# Main.net
KiCad netlist of a schematic drawn in Altium Designer
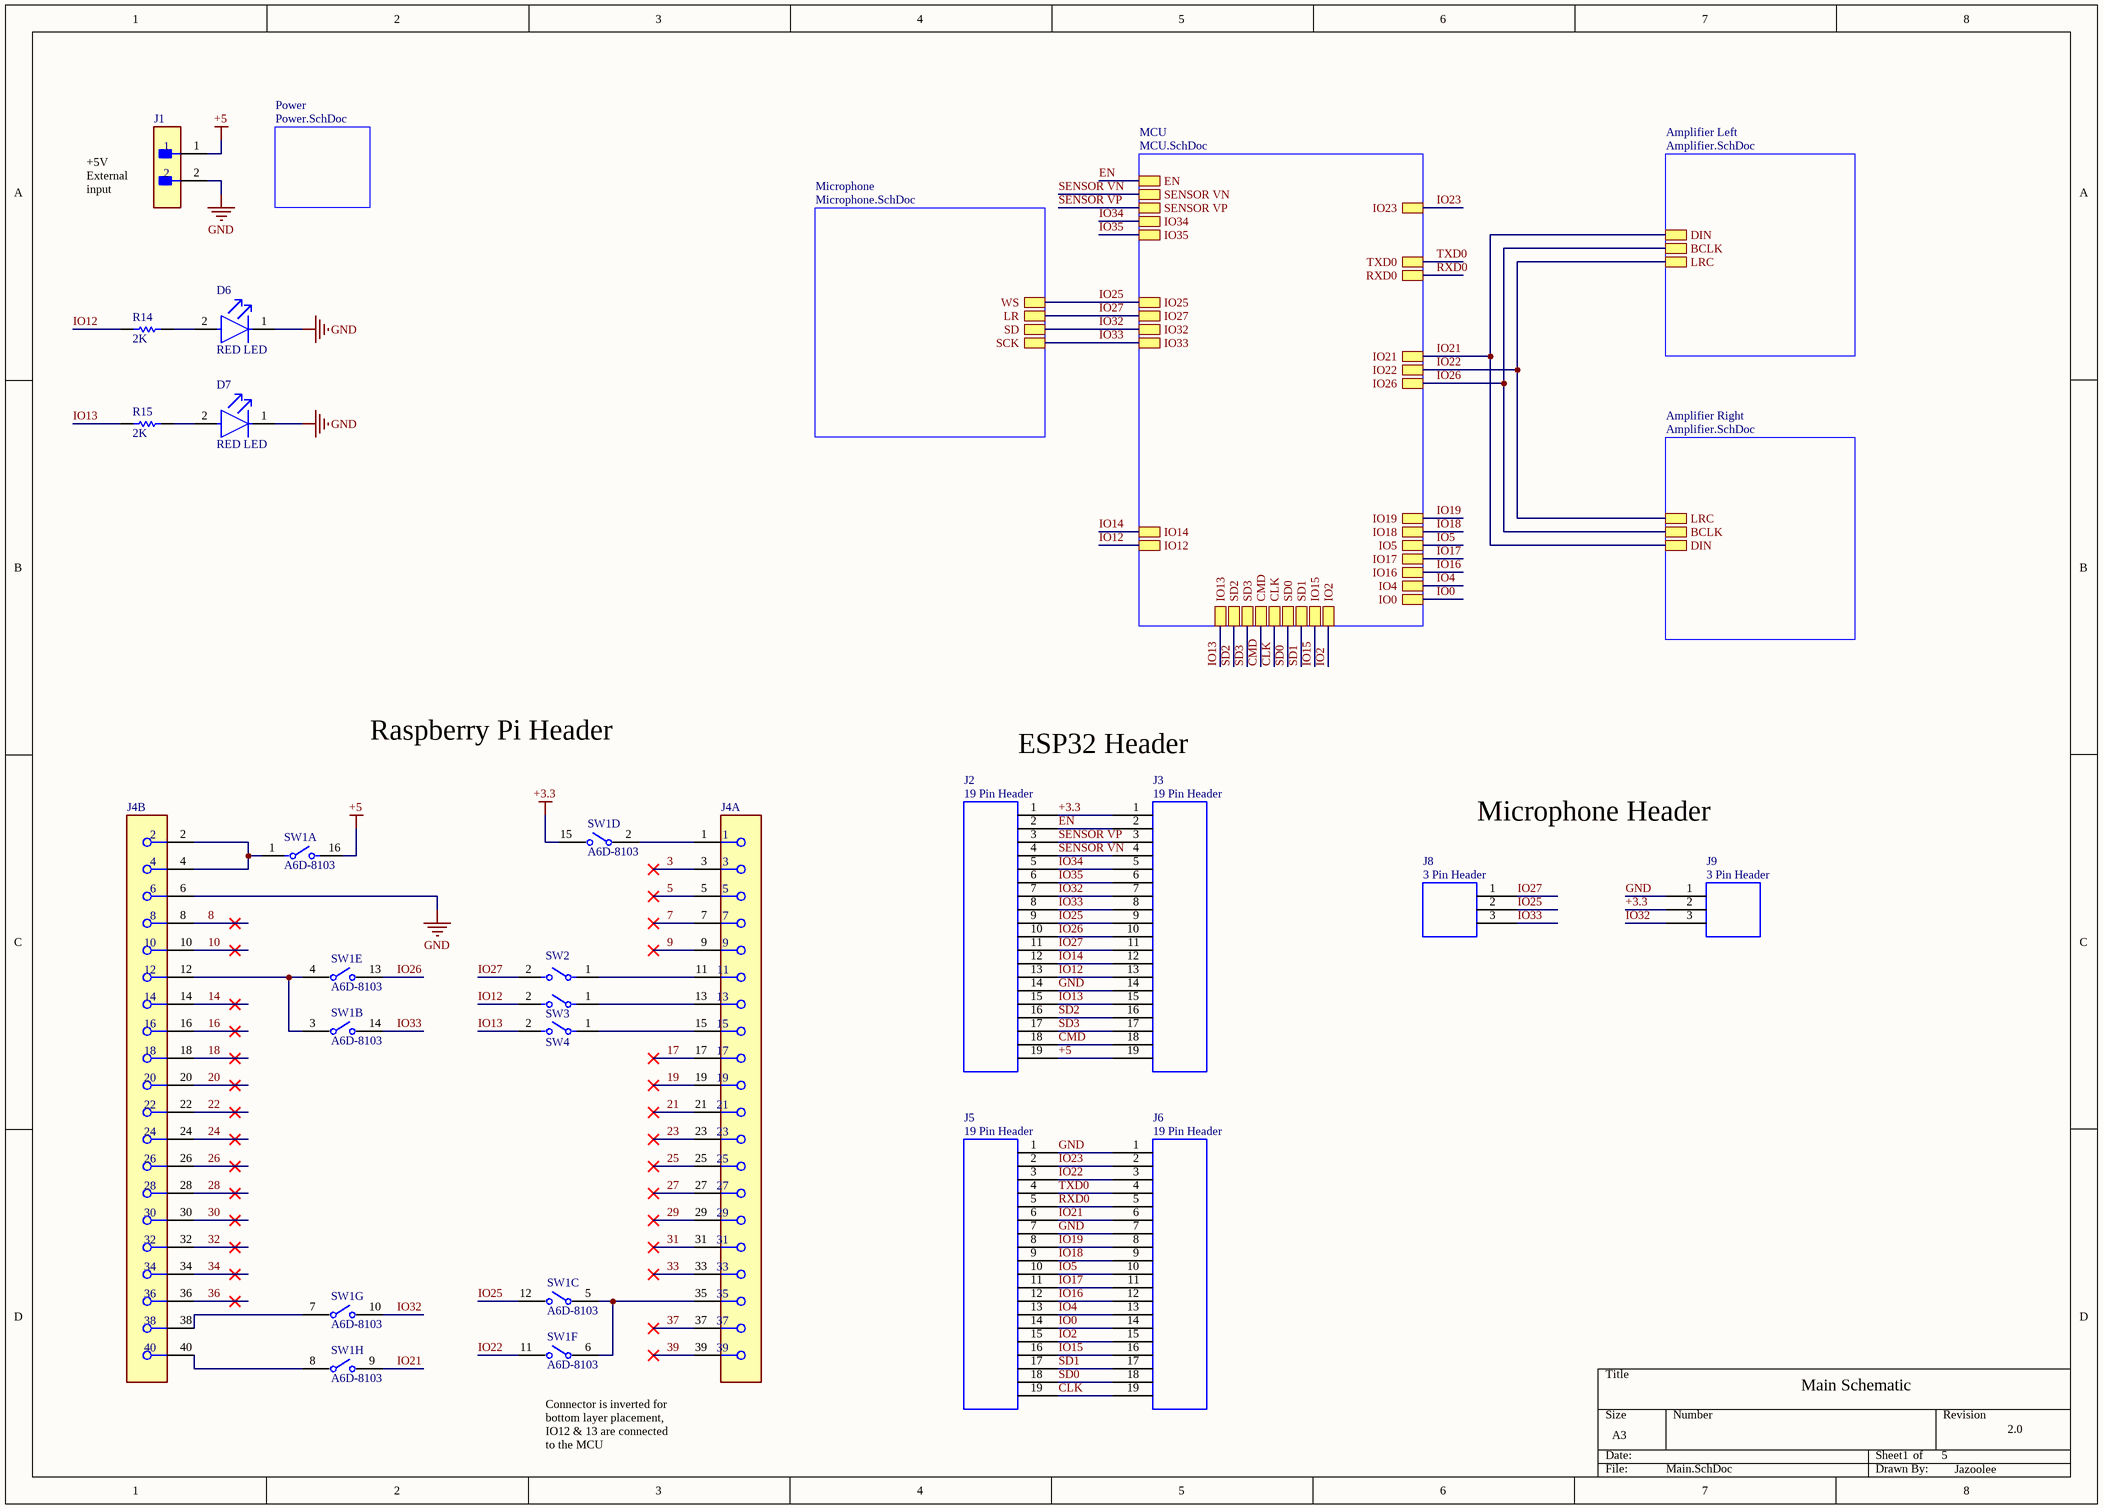
[diagram p0: Main.SchDoc]

(export (version "E")
  (design (tool "Eeschema 10.0.6"))
  (components
    (comp (ref "D6")
      (value "HSMS-C150")
      (footprint "FP-HSMS-C150-MFG")
      (description "LED RED")
      (fields (field (name "COLOR") "RED LED"))
      (libsource (lib "Altium Content Vault") (part "8706943c75ba83719d021d2fdc84c58"))
    )
    (comp (ref "D7")
      (value "HSMS-C150")
      (footprint "FP-HSMS-C150-MFG")
      (description "LED RED")
      (fields (field (name "COLOR") "RED LED"))
      (libsource (lib "Altium Content Vault") (part "8706943c75ba83719d021d2fdc84c58"))
    )
    (comp (ref "J1")
      (value "B2B-XH-A(LF)(SN)")
      (footprint "FP-B2B-XH-A_LF_SN-MFG")
      (description "CONN HEADER VERT 2POS 2.5MM")
      (libsource (lib "Altium Content Vault") (part "3bc925449376181038e59eaffc5286c"))
    )
    (comp (ref "J2")
      (value "19 Pin Header")
      (footprint "19 Pin Header")
      (libsource (lib "Schlib1") (part "19 Pin Header"))
    )
    (comp (ref "J3")
      (value "19 Pin Header")
      (footprint "19 Pin Header")
      (libsource (lib "Schlib1") (part "19 Pin Header"))
    )
    (comp (ref "J4")
      (value "SFH11-PBPC-D20-ST-BK")
      (footprint "FP-SFH11-PBPC-D20-ST-BK-MFG")
      (description "CONN HDR 40POS 0.1 GOLD PCB")
      (libsource (lib "Altium Content Vault") (part "7acf1c4a8db21028d11741a46a6ec78"))
    )
    (comp (ref "J5")
      (value "19 Pin Header")
      (footprint "19 Pin Header")
      (libsource (lib "Schlib1") (part "19 Pin Header"))
    )
    (comp (ref "J6")
      (value "19 Pin Header")
      (footprint "19 Pin Header")
      (libsource (lib "Schlib1") (part "19 Pin Header"))
    )
    (comp (ref "J8")
      (value "3 Pin Header")
      (footprint "3 Pin Header")
      (libsource (lib "Schlib1") (part "3 Pin Header"))
    )
    (comp (ref "J9")
      (value "3 Pin Header")
      (footprint "3 Pin Header")
      (libsource (lib "Schlib1") (part "3 Pin Header"))
    )
    (comp (ref "R14")
      (value "2K")
      (footprint "RESC2013X60X35LL10T20")
      (fields (field (name "PART NUMBER") "RT0805FRE072KL") (field (name "MANUFACTURER") "Yageo"))
      (libsource (lib "Altium Content Vault") (part "RES"))
    )
    (comp (ref "R15")
      (value "2K")
      (footprint "RESC2013X60X35LL10T20")
      (fields (field (name "PART NUMBER") "RT0805FRE072KL") (field (name "MANUFACTURER") "Yageo"))
      (libsource (lib "Altium Content Vault") (part "RES"))
    )
    (comp (ref "SW1")
      (value "A6D-8103")
      (footprint "FP-A6D-8103-MFG")
      (description "SWITCH SLIDE DIP SPST 30MA 30V")
      (fields
        (field (name "MANUFACTURER") "Omron Electronics Inc-EMC Div")
        (field (name "OCTOPART") "https://octopart.com/a6d-8103-omron-134189")
      )
      (libsource (lib "Altium Content Vault") (part "05751733197cf25f22959cb843bf489"))
    )
    (comp (ref "SW2")
      (value "BD01")
      (footprint "FP-BD01-MFG")
      (description "SWITCH SLIDE DIP SPST 100MA 5V")
      (libsource (lib "Altium Content Vault") (part "bb27bde45df87f1f469753f287ef5ae"))
    )
    (comp (ref "SW3")
      (value "BD01")
      (footprint "FP-BD01-MFG")
      (description "SWITCH SLIDE DIP SPST 100MA 5V")
      (libsource (lib "Altium Content Vault") (part "bb27bde45df87f1f469753f287ef5ae"))
    )
    (comp (ref "SW4")
      (value "BD01")
      (footprint "FP-BD01-MFG")
      (description "SWITCH SLIDE DIP SPST 100MA 5V")
      (libsource (lib "Altium Content Vault") (part "bb27bde45df87f1f469753f287ef5ae"))
    )
  )
  (nets
    (net (code "1") (name "+3.3") (class "Default")
      (node (ref "J2") (pin "1") (pinfunction "1_1") (pintype "passive"))
      (node (ref "J3") (pin "1") (pinfunction "1_1") (pintype "passive"))
      (node (ref "J9") (pin "2") (pinfunction "2_2") (pintype "passive"))
      (node (ref "SW1") (pin "15") (pinfunction "15_15") (pintype "passive"))
    )
    (net (code "2") (name "+5") (class "Default")
      (node (ref "J1") (pin "1") (pinfunction "1_1") (pintype "passive"))
      (node (ref "J2") (pin "19") (pinfunction "19_19") (pintype "passive"))
      (node (ref "J3") (pin "19") (pinfunction "19_19") (pintype "passive"))
      (node (ref "SW1") (pin "16") (pinfunction "16_16") (pintype "passive"))
    )
    (net (code "3") (name "/3") (class "Default")
      (node (ref "J4") (pin "3") (pinfunction "3_3") (pintype "passive+no_connect"))
    )
    (net (code "4") (name "/5") (class "Default")
      (node (ref "J4") (pin "5") (pinfunction "5_5") (pintype "passive+no_connect"))
    )
    (net (code "5") (name "/7") (class "Default")
      (node (ref "J4") (pin "7") (pinfunction "7_7") (pintype "passive+no_connect"))
    )
    (net (code "6") (name "/8") (class "Default")
      (node (ref "J4") (pin "8") (pinfunction "8_8") (pintype "passive"))
    )
    (net (code "7") (name "/9") (class "Default")
      (node (ref "J4") (pin "9") (pinfunction "9_9") (pintype "passive+no_connect"))
    )
    (net (code "8") (name "/10") (class "Default")
      (node (ref "J4") (pin "10") (pinfunction "10_10") (pintype "passive"))
    )
    (net (code "9") (name "/14") (class "Default")
      (node (ref "J4") (pin "14") (pinfunction "14_14") (pintype "passive"))
    )
    (net (code "10") (name "/16") (class "Default")
      (node (ref "J4") (pin "16") (pinfunction "16_16") (pintype "passive"))
    )
    (net (code "11") (name "/17") (class "Default")
      (node (ref "J4") (pin "17") (pinfunction "17_17") (pintype "passive+no_connect"))
    )
    (net (code "12") (name "/18") (class "Default")
      (node (ref "J4") (pin "18") (pinfunction "18_18") (pintype "passive"))
    )
    (net (code "13") (name "/19") (class "Default")
      (node (ref "J4") (pin "19") (pinfunction "19_19") (pintype "passive+no_connect"))
    )
    (net (code "14") (name "/20") (class "Default")
      (node (ref "J4") (pin "20") (pinfunction "20_20") (pintype "passive"))
    )
    (net (code "15") (name "/21") (class "Default")
      (node (ref "J4") (pin "21") (pinfunction "21_21") (pintype "passive+no_connect"))
    )
    (net (code "16") (name "/22") (class "Default")
      (node (ref "J4") (pin "22") (pinfunction "22_22") (pintype "passive"))
    )
    (net (code "17") (name "/23") (class "Default")
      (node (ref "J4") (pin "23") (pinfunction "23_23") (pintype "passive+no_connect"))
    )
    (net (code "18") (name "/24") (class "Default")
      (node (ref "J4") (pin "24") (pinfunction "24_24") (pintype "passive"))
    )
    (net (code "19") (name "/25") (class "Default")
      (node (ref "J4") (pin "25") (pinfunction "25_25") (pintype "passive+no_connect"))
    )
    (net (code "20") (name "/26") (class "Default")
      (node (ref "J4") (pin "26") (pinfunction "26_26") (pintype "passive"))
    )
    (net (code "21") (name "/27") (class "Default")
      (node (ref "J4") (pin "27") (pinfunction "27_27") (pintype "passive+no_connect"))
    )
    (net (code "22") (name "/28") (class "Default")
      (node (ref "J4") (pin "28") (pinfunction "28_28") (pintype "passive"))
    )
    (net (code "23") (name "/29") (class "Default")
      (node (ref "J4") (pin "29") (pinfunction "29_29") (pintype "passive+no_connect"))
    )
    (net (code "24") (name "/30") (class "Default")
      (node (ref "J4") (pin "30") (pinfunction "30_30") (pintype "passive"))
    )
    (net (code "25") (name "/31") (class "Default")
      (node (ref "J4") (pin "31") (pinfunction "31_31") (pintype "passive+no_connect"))
    )
    (net (code "26") (name "/32") (class "Default")
      (node (ref "J4") (pin "32") (pinfunction "32_32") (pintype "passive"))
    )
    (net (code "27") (name "/33") (class "Default")
      (node (ref "J4") (pin "33") (pinfunction "33_33") (pintype "passive+no_connect"))
    )
    (net (code "28") (name "/34") (class "Default")
      (node (ref "J4") (pin "34") (pinfunction "34_34") (pintype "passive"))
    )
    (net (code "29") (name "/36") (class "Default")
      (node (ref "J4") (pin "36") (pinfunction "36_36") (pintype "passive"))
    )
    (net (code "30") (name "/37") (class "Default")
      (node (ref "J4") (pin "37") (pinfunction "37_37") (pintype "passive+no_connect"))
    )
    (net (code "31") (name "/39") (class "Default")
      (node (ref "J4") (pin "39") (pinfunction "39_39") (pintype "passive+no_connect"))
    )
    (net (code "32") (name "/CLK") (class "Default")
      (node (ref "J5") (pin "19") (pinfunction "19_19") (pintype "passive"))
      (node (ref "J6") (pin "19") (pinfunction "19_19") (pintype "passive"))
    )
    (net (code "33") (name "/CMD") (class "Default")
      (node (ref "J2") (pin "18") (pinfunction "18_18") (pintype "passive"))
      (node (ref "J3") (pin "18") (pinfunction "18_18") (pintype "passive"))
    )
    (net (code "34") (name "/EN") (class "Default")
      (node (ref "J2") (pin "2") (pinfunction "2_2") (pintype "passive"))
      (node (ref "J3") (pin "2") (pinfunction "2_2") (pintype "passive"))
    )
    (net (code "35") (name "/IO0") (class "Default")
      (node (ref "J5") (pin "14") (pinfunction "14_14") (pintype "passive"))
      (node (ref "J6") (pin "14") (pinfunction "14_14") (pintype "passive"))
    )
    (net (code "36") (name "/IO2") (class "Default")
      (node (ref "J5") (pin "15") (pinfunction "15_15") (pintype "passive"))
      (node (ref "J6") (pin "15") (pinfunction "15_15") (pintype "passive"))
    )
    (net (code "37") (name "/IO4") (class "Default")
      (node (ref "J5") (pin "13") (pinfunction "13_13") (pintype "passive"))
      (node (ref "J6") (pin "13") (pinfunction "13_13") (pintype "passive"))
    )
    (net (code "38") (name "/IO5") (class "Default")
      (node (ref "J5") (pin "10") (pinfunction "10_10") (pintype "passive"))
      (node (ref "J6") (pin "10") (pinfunction "10_10") (pintype "passive"))
    )
    (net (code "39") (name "/IO12") (class "Default")
      (node (ref "J2") (pin "13") (pinfunction "13_13") (pintype "passive"))
      (node (ref "J3") (pin "13") (pinfunction "13_13") (pintype "passive"))
      (node (ref "R14") (pin "2") (pinfunction "2_2") (pintype "passive"))
      (node (ref "SW3") (pin "2") (pinfunction "2_2") (pintype "passive"))
    )
    (net (code "40") (name "/IO13") (class "Default")
      (node (ref "J2") (pin "15") (pinfunction "15_15") (pintype "passive"))
      (node (ref "J3") (pin "15") (pinfunction "15_15") (pintype "passive"))
      (node (ref "R15") (pin "2") (pinfunction "2_2") (pintype "passive"))
      (node (ref "SW4") (pin "2") (pinfunction "2_2") (pintype "passive"))
    )
    (net (code "41") (name "/IO14") (class "Default")
      (node (ref "J2") (pin "12") (pinfunction "12_12") (pintype "passive"))
      (node (ref "J3") (pin "12") (pinfunction "12_12") (pintype "passive"))
    )
    (net (code "42") (name "/IO15") (class "Default")
      (node (ref "J5") (pin "16") (pinfunction "16_16") (pintype "passive"))
      (node (ref "J6") (pin "16") (pinfunction "16_16") (pintype "passive"))
    )
    (net (code "43") (name "/IO16") (class "Default")
      (node (ref "J5") (pin "12") (pinfunction "12_12") (pintype "passive"))
      (node (ref "J6") (pin "12") (pinfunction "12_12") (pintype "passive"))
    )
    (net (code "44") (name "/IO17") (class "Default")
      (node (ref "J5") (pin "11") (pinfunction "11_11") (pintype "passive"))
      (node (ref "J6") (pin "11") (pinfunction "11_11") (pintype "passive"))
    )
    (net (code "45") (name "/IO18") (class "Default")
      (node (ref "J5") (pin "9") (pinfunction "9_9") (pintype "passive"))
      (node (ref "J6") (pin "9") (pinfunction "9_9") (pintype "passive"))
    )
    (net (code "46") (name "/IO19") (class "Default")
      (node (ref "J5") (pin "8") (pinfunction "8_8") (pintype "passive"))
      (node (ref "J6") (pin "8") (pinfunction "8_8") (pintype "passive"))
    )
    (net (code "47") (name "/IO21") (class "Default")
      (node (ref "J5") (pin "6") (pinfunction "6_6") (pintype "passive"))
      (node (ref "J6") (pin "6") (pinfunction "6_6") (pintype "passive"))
      (node (ref "SW1") (pin "9") (pinfunction "9_9") (pintype "passive"))
    )
    (net (code "48") (name "/IO22") (class "Default")
      (node (ref "J5") (pin "3") (pinfunction "3_3") (pintype "passive"))
      (node (ref "J6") (pin "3") (pinfunction "3_3") (pintype "passive"))
      (node (ref "SW1") (pin "11") (pinfunction "11_11") (pintype "passive"))
    )
    (net (code "49") (name "/IO23") (class "Default")
      (node (ref "J5") (pin "2") (pinfunction "2_2") (pintype "passive"))
      (node (ref "J6") (pin "2") (pinfunction "2_2") (pintype "passive"))
    )
    (net (code "50") (name "/IO25") (class "Default")
      (node (ref "J2") (pin "9") (pinfunction "9_9") (pintype "passive"))
      (node (ref "J3") (pin "9") (pinfunction "9_9") (pintype "passive"))
      (node (ref "J8") (pin "2") (pinfunction "2_2") (pintype "passive"))
      (node (ref "SW1") (pin "12") (pinfunction "12_12") (pintype "passive"))
    )
    (net (code "51") (name "/IO26") (class "Default")
      (node (ref "J2") (pin "10") (pinfunction "10_10") (pintype "passive"))
      (node (ref "J3") (pin "10") (pinfunction "10_10") (pintype "passive"))
      (node (ref "SW1") (pin "13") (pinfunction "13_13") (pintype "passive"))
    )
    (net (code "52") (name "/IO27") (class "Default")
      (node (ref "J2") (pin "11") (pinfunction "11_11") (pintype "passive"))
      (node (ref "J3") (pin "11") (pinfunction "11_11") (pintype "passive"))
      (node (ref "J8") (pin "1") (pinfunction "1_1") (pintype "passive"))
      (node (ref "SW2") (pin "2") (pinfunction "2_2") (pintype "passive"))
    )
    (net (code "53") (name "/IO32") (class "Default")
      (node (ref "J2") (pin "7") (pinfunction "7_7") (pintype "passive"))
      (node (ref "J3") (pin "7") (pinfunction "7_7") (pintype "passive"))
      (node (ref "J9") (pin "3") (pinfunction "3_3") (pintype "passive"))
      (node (ref "SW1") (pin "10") (pinfunction "10_10") (pintype "passive"))
    )
    (net (code "54") (name "/IO33") (class "Default")
      (node (ref "J2") (pin "8") (pinfunction "8_8") (pintype "passive"))
      (node (ref "J3") (pin "8") (pinfunction "8_8") (pintype "passive"))
      (node (ref "J8") (pin "3") (pinfunction "3_3") (pintype "passive"))
      (node (ref "SW1") (pin "14") (pinfunction "14_14") (pintype "passive"))
    )
    (net (code "55") (name "/IO34") (class "Default")
      (node (ref "J2") (pin "5") (pinfunction "5_5") (pintype "passive"))
      (node (ref "J3") (pin "5") (pinfunction "5_5") (pintype "passive"))
    )
    (net (code "56") (name "/IO35") (class "Default")
      (node (ref "J2") (pin "6") (pinfunction "6_6") (pintype "passive"))
      (node (ref "J3") (pin "6") (pinfunction "6_6") (pintype "passive"))
    )
    (net (code "57") (name "/RXD0") (class "Default")
      (node (ref "J5") (pin "5") (pinfunction "5_5") (pintype "passive"))
      (node (ref "J6") (pin "5") (pinfunction "5_5") (pintype "passive"))
    )
    (net (code "58") (name "/SD0") (class "Default")
      (node (ref "J5") (pin "18") (pinfunction "18_18") (pintype "passive"))
      (node (ref "J6") (pin "18") (pinfunction "18_18") (pintype "passive"))
    )
    (net (code "59") (name "/SD1") (class "Default")
      (node (ref "J5") (pin "17") (pinfunction "17_17") (pintype "passive"))
      (node (ref "J6") (pin "17") (pinfunction "17_17") (pintype "passive"))
    )
    (net (code "60") (name "/SD2") (class "Default")
      (node (ref "J2") (pin "16") (pinfunction "16_16") (pintype "passive"))
      (node (ref "J3") (pin "16") (pinfunction "16_16") (pintype "passive"))
    )
    (net (code "61") (name "/SD3") (class "Default")
      (node (ref "J2") (pin "17") (pinfunction "17_17") (pintype "passive"))
      (node (ref "J3") (pin "17") (pinfunction "17_17") (pintype "passive"))
    )
    (net (code "62") (name "/SENSOR VN") (class "Default")
      (node (ref "J2") (pin "4") (pinfunction "4_4") (pintype "passive"))
      (node (ref "J3") (pin "4") (pinfunction "4_4") (pintype "passive"))
    )
    (net (code "63") (name "/SENSOR VP") (class "Default")
      (node (ref "J2") (pin "3") (pinfunction "3_3") (pintype "passive"))
      (node (ref "J3") (pin "3") (pinfunction "3_3") (pintype "passive"))
    )
    (net (code "64") (name "/TXD0") (class "Default")
      (node (ref "J5") (pin "4") (pinfunction "4_4") (pintype "passive"))
      (node (ref "J6") (pin "4") (pinfunction "4_4") (pintype "passive"))
    )
    (net (code "65") (name "GND") (class "Default")
      (node (ref "D6") (pin "1") (pinfunction "C_1") (pintype "passive"))
      (node (ref "D7") (pin "1") (pinfunction "C_1") (pintype "passive"))
      (node (ref "J1") (pin "2") (pinfunction "2_2") (pintype "passive"))
      (node (ref "J2") (pin "14") (pinfunction "14_14") (pintype "passive"))
      (node (ref "J3") (pin "14") (pinfunction "14_14") (pintype "passive"))
      (node (ref "J4") (pin "6") (pinfunction "6_6") (pintype "passive"))
      (node (ref "J5") (pin "1") (pinfunction "1_1") (pintype "passive"))
      (node (ref "J5") (pin "7") (pinfunction "7_7") (pintype "passive"))
      (node (ref "J6") (pin "1") (pinfunction "1_1") (pintype "passive"))
      (node (ref "J6") (pin "7") (pinfunction "7_7") (pintype "passive"))
      (node (ref "J9") (pin "1") (pinfunction "1_1") (pintype "passive"))
    )
    (net (code "66") (name "Net-(D6-A)") (class "Default")
      (node (ref "D6") (pin "2") (pinfunction "A_2") (pintype "passive"))
      (node (ref "R14") (pin "1") (pinfunction "1_1") (pintype "passive"))
    )
    (net (code "67") (name "Net-(D7-A)") (class "Default")
      (node (ref "D7") (pin "2") (pinfunction "A_2") (pintype "passive"))
      (node (ref "R15") (pin "1") (pinfunction "1_1") (pintype "passive"))
    )
    (net (code "68") (name "Net-(J4-Pad1)") (class "Default")
      (node (ref "J4") (pin "1") (pinfunction "1_1") (pintype "passive"))
      (node (ref "SW1") (pin "2") (pinfunction "2_2") (pintype "passive"))
    )
    (net (code "69") (name "Net-(J4-Pad2)") (class "Default")
      (node (ref "J4") (pin "2") (pinfunction "2_2") (pintype "passive"))
      (node (ref "J4") (pin "4") (pinfunction "4_4") (pintype "passive"))
      (node (ref "SW1") (pin "1") (pinfunction "1_1") (pintype "passive"))
    )
    (net (code "70") (name "Net-(J4-Pad11)") (class "Default")
      (node (ref "J4") (pin "11") (pinfunction "11_11") (pintype "passive"))
      (node (ref "SW2") (pin "1") (pinfunction "1_1") (pintype "passive"))
    )
    (net (code "71") (name "Net-(J4-Pad12)") (class "Default")
      (node (ref "J4") (pin "12") (pinfunction "12_12") (pintype "passive"))
      (node (ref "SW1") (pin "3") (pinfunction "3_3") (pintype "passive"))
      (node (ref "SW1") (pin "4") (pinfunction "4_4") (pintype "passive"))
    )
    (net (code "72") (name "Net-(J4-Pad13)") (class "Default")
      (node (ref "J4") (pin "13") (pinfunction "13_13") (pintype "passive"))
      (node (ref "SW3") (pin "1") (pinfunction "1_1") (pintype "passive"))
    )
    (net (code "73") (name "Net-(J4-Pad15)") (class "Default")
      (node (ref "J4") (pin "15") (pinfunction "15_15") (pintype "passive"))
      (node (ref "SW4") (pin "1") (pinfunction "1_1") (pintype "passive"))
    )
    (net (code "74") (name "Net-(J4-Pad35)") (class "Default")
      (node (ref "J4") (pin "35") (pinfunction "35_35") (pintype "passive"))
      (node (ref "SW1") (pin "5") (pinfunction "5_5") (pintype "passive"))
      (node (ref "SW1") (pin "6") (pinfunction "6_6") (pintype "passive"))
    )
    (net (code "75") (name "Net-(J4-Pad38)") (class "Default")
      (node (ref "J4") (pin "38") (pinfunction "38_38") (pintype "passive"))
      (node (ref "SW1") (pin "7") (pinfunction "7_7") (pintype "passive"))
    )
    (net (code "76") (name "Net-(J4-Pad40)") (class "Default")
      (node (ref "J4") (pin "40") (pinfunction "40_40") (pintype "passive"))
      (node (ref "SW1") (pin "8") (pinfunction "8_8") (pintype "passive"))
    )
  )
)
